# edges_expander_v01.net
KiCad netlist of a schematic drawn in EAGLE
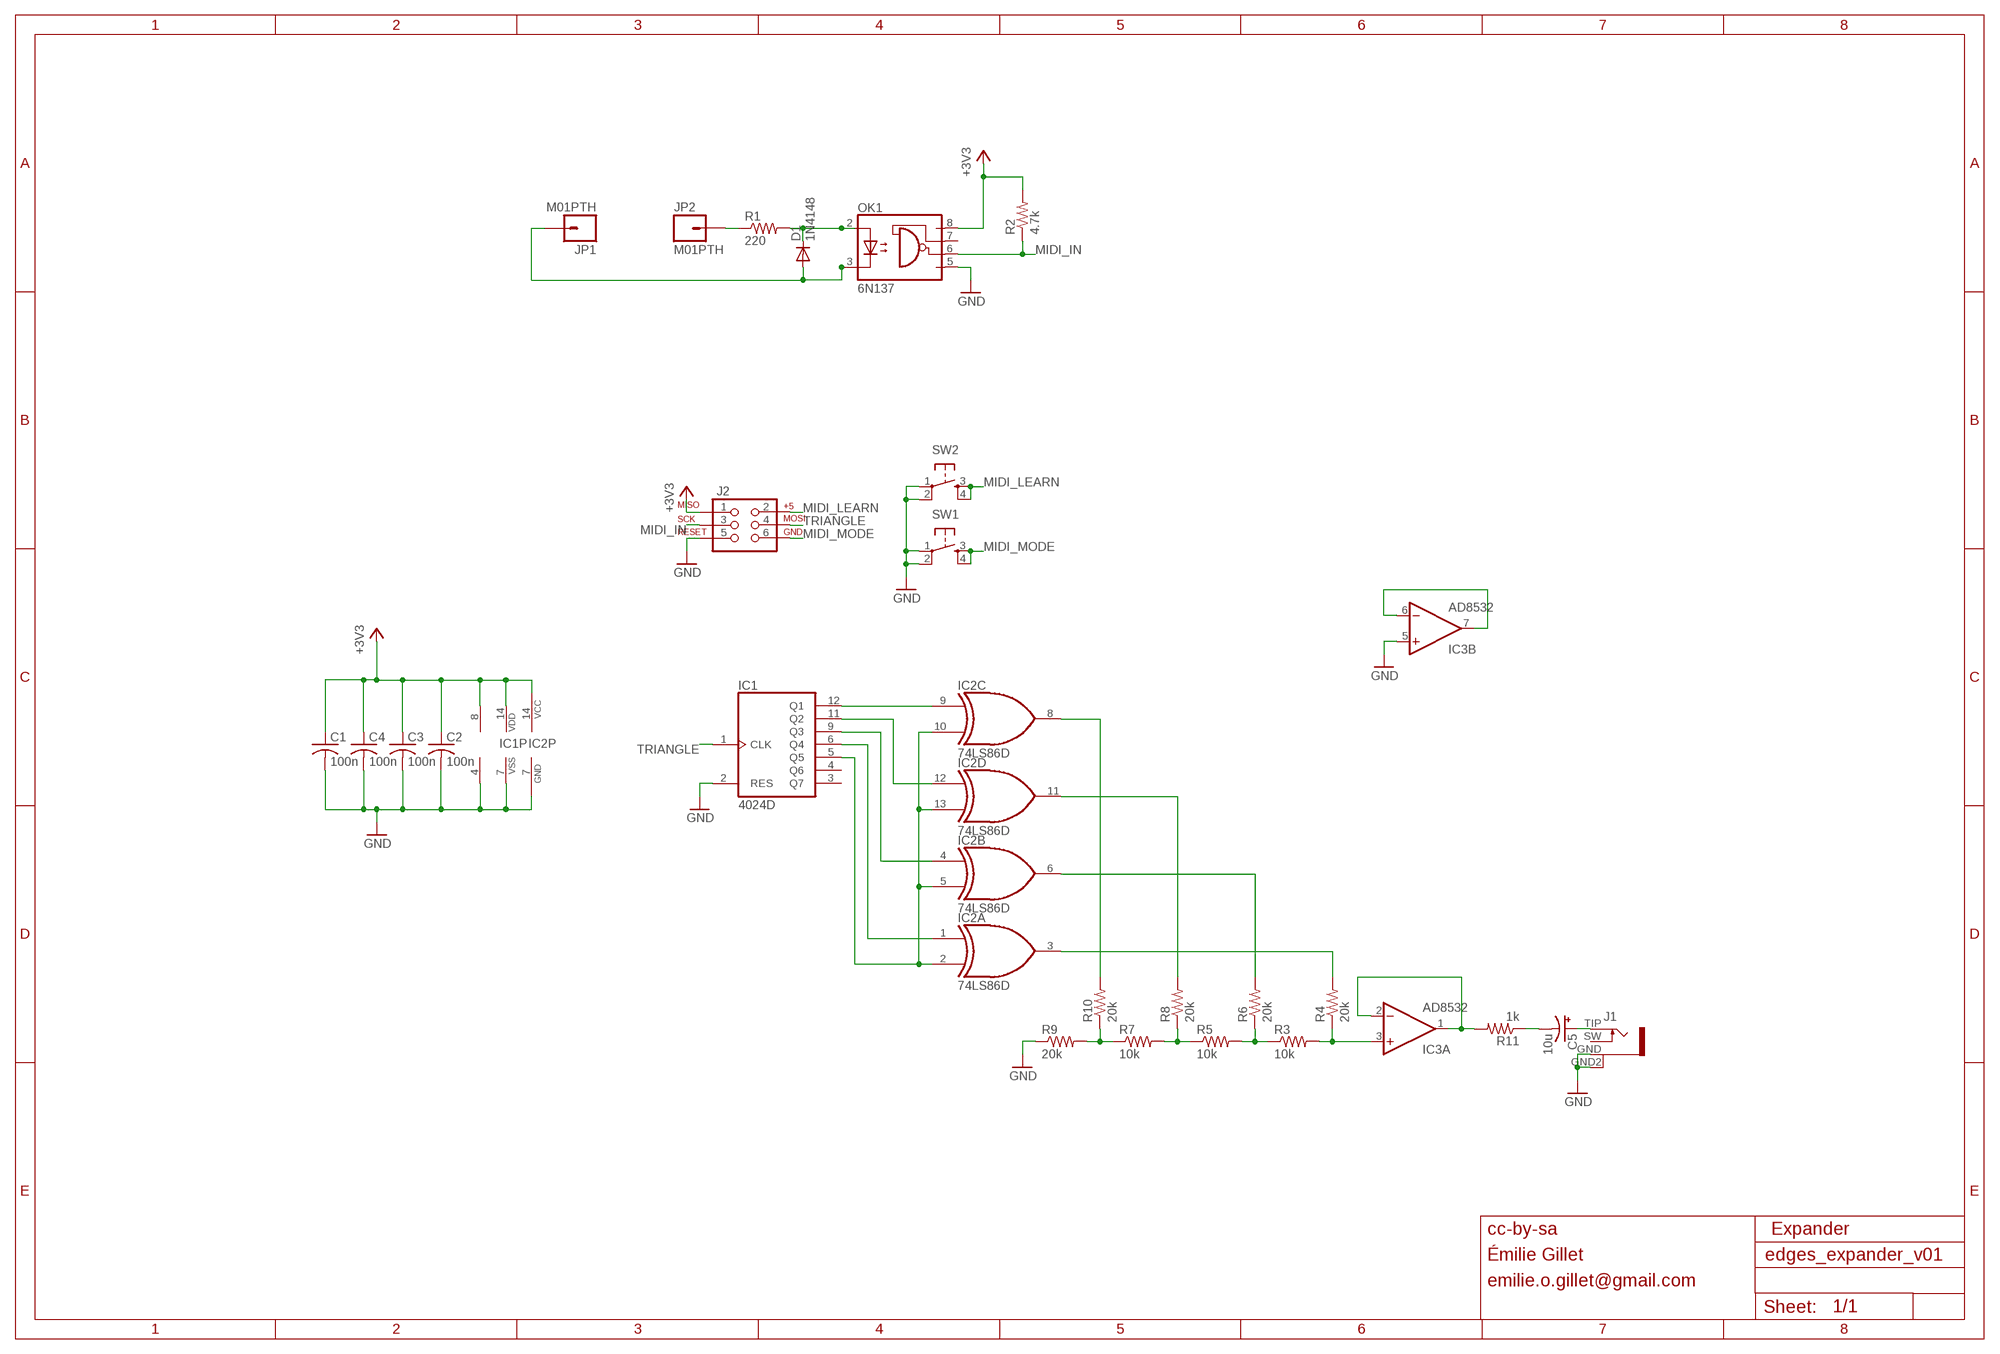
[diagram p0: schematic, sheet 1]

(export (version "E")
  (design (tool "Eeschema 10.0.6"))
  (components
    (comp (ref "C1")
      (value "100n")
      (footprint "eagle-import:C0603")
      (libsource (lib "eagle-import") (part "C-USC0603"))
    )
    (comp (ref "C2")
      (value "100n")
      (footprint "eagle-import:C0603")
      (libsource (lib "eagle-import") (part "C-USC0603"))
    )
    (comp (ref "C3")
      (value "100n")
      (footprint "eagle-import:C0603")
      (libsource (lib "eagle-import") (part "C-USC0603"))
    )
    (comp (ref "C4")
      (value "100n")
      (footprint "eagle-import:C0603")
      (libsource (lib "eagle-import") (part "C-USC0603"))
    )
    (comp (ref "C5")
      (value "10u")
      (footprint "eagle-import:PANASONIC_B")
      (libsource (lib "eagle-import") (part "CPOL-USB"))
    )
    (comp (ref "D1")
      (value "1N4148")
      (footprint "eagle-import:SOD323-W")
      (libsource (lib "eagle-import") (part "DIODE-SOD323-W"))
    )
    (comp (ref "IC1")
      (value "4024D")
      (footprint "eagle-import:SO14")
      (libsource (lib "eagle-import") (part "4024D"))
    )
    (comp (ref "IC2")
      (value "74LS86D")
      (footprint "eagle-import:SO14")
      (libsource (lib "eagle-import") (part "7486DLS"))
    )
    (comp (ref "IC3")
      (value "AD8532")
      (footprint "eagle-import:SO08")
      (libsource (lib "eagle-import") (part "TL072D"))
    )
    (comp (ref "J1")
      (value "PJ301WQP")
      (footprint "eagle-import:WQP_PJ_301BM")
      (libsource (lib "eagle-import") (part "PJ301WQP"))
    )
    (comp (ref "J2")
      (value "AVR_SPI_PRG_6PTH")
      (footprint "eagle-import:2X3")
      (libsource (lib "eagle-import") (part "AVR_SPI_PRG_6PTH"))
    )
    (comp (ref "JP1")
      (value "M01PTH")
      (footprint "eagle-import:1X01")
      (libsource (lib "eagle-import") (part "M01PTH"))
    )
    (comp (ref "JP2")
      (value "M01PTH")
      (footprint "eagle-import:1X01")
      (libsource (lib "eagle-import") (part "M01PTH"))
    )
    (comp (ref "OK1")
      (value "6N137")
      (footprint "eagle-import:DIL8-SMD")
      (libsource (lib "eagle-import") (part "6N137SMT"))
    )
    (comp (ref "R1")
      (value "220")
      (footprint "eagle-import:R0603")
      (libsource (lib "eagle-import") (part "R-US_R0603"))
    )
    (comp (ref "R2")
      (value "4.7k")
      (footprint "eagle-import:R0603")
      (libsource (lib "eagle-import") (part "R-US_R0603"))
    )
    (comp (ref "R3")
      (value "10k")
      (footprint "eagle-import:R0603")
      (libsource (lib "eagle-import") (part "R-US_R0603"))
    )
    (comp (ref "R4")
      (value "20k")
      (footprint "eagle-import:R0603")
      (libsource (lib "eagle-import") (part "R-US_R0603"))
    )
    (comp (ref "R5")
      (value "10k")
      (footprint "eagle-import:R0603")
      (libsource (lib "eagle-import") (part "R-US_R0603"))
    )
    (comp (ref "R6")
      (value "20k")
      (footprint "eagle-import:R0603")
      (libsource (lib "eagle-import") (part "R-US_R0603"))
    )
    (comp (ref "R7")
      (value "10k")
      (footprint "eagle-import:R0603")
      (libsource (lib "eagle-import") (part "R-US_R0603"))
    )
    (comp (ref "R8")
      (value "20k")
      (footprint "eagle-import:R0603")
      (libsource (lib "eagle-import") (part "R-US_R0603"))
    )
    (comp (ref "R9")
      (value "20k")
      (footprint "eagle-import:R0603")
      (libsource (lib "eagle-import") (part "R-US_R0603"))
    )
    (comp (ref "R10")
      (value "20k")
      (footprint "eagle-import:R0603")
      (libsource (lib "eagle-import") (part "R-US_R0603"))
    )
    (comp (ref "R11")
      (value "1k")
      (footprint "eagle-import:R0603")
      (libsource (lib "eagle-import") (part "R-US_R0603"))
    )
    (comp (ref "SW1")
      (value "TAC_SWITCHPTH")
      (footprint "eagle-import:TACTILE-PTH")
      (libsource (lib "eagle-import") (part "TAC_SWITCHPTH"))
    )
    (comp (ref "SW2")
      (value "TAC_SWITCHPTH")
      (footprint "eagle-import:TACTILE-PTH")
      (libsource (lib "eagle-import") (part "TAC_SWITCHPTH"))
    )
  )
  (nets
    (net (code "1") (name "+3V3") (class "Default")
      (node (ref "C1") (pin "1") (pinfunction "1_1") (pintype "passive"))
      (node (ref "C2") (pin "1") (pinfunction "1_1") (pintype "passive"))
      (node (ref "C3") (pin "1") (pinfunction "1_1") (pintype "passive"))
      (node (ref "C4") (pin "1") (pinfunction "1_1") (pintype "passive"))
      (node (ref "IC1") (pin "14") (pinfunction "VDD_14") (pintype "power_in"))
      (node (ref "IC2") (pin "14") (pinfunction "VCC_14") (pintype "power_in"))
      (node (ref "IC3") (pin "8") (pinfunction "V+_8") (pintype "power_in"))
      (node (ref "J2") (pin "1") (pinfunction "1_1") (pintype "passive"))
      (node (ref "OK1") (pin "8") (pinfunction "VCC_8") (pintype "passive"))
      (node (ref "R2") (pin "2") (pinfunction "2_2") (pintype "passive"))
    )
    (net (code "2") (name "/MIDI_IN") (class "Default")
      (node (ref "J2") (pin "3") (pinfunction "3_3") (pintype "passive"))
      (node (ref "OK1") (pin "6") (pinfunction "VO_6") (pintype "passive"))
      (node (ref "R2") (pin "1") (pinfunction "1_1") (pintype "passive"))
    )
    (net (code "3") (name "/MIDI_LEARN") (class "Default")
      (node (ref "J2") (pin "2") (pinfunction "2_2") (pintype "passive"))
      (node (ref "SW2") (pin "3") (pinfunction "3_3") (pintype "passive"))
      (node (ref "SW2") (pin "4") (pinfunction "4_4") (pintype "passive"))
    )
    (net (code "4") (name "/MIDI_MODE") (class "Default")
      (node (ref "J2") (pin "6") (pinfunction "6_6") (pintype "passive"))
      (node (ref "SW1") (pin "3") (pinfunction "3_3") (pintype "passive"))
      (node (ref "SW1") (pin "4") (pinfunction "4_4") (pintype "passive"))
    )
    (net (code "5") (name "/TRIANGLE") (class "Default")
      (node (ref "IC1") (pin "1") (pinfunction "CLK_1") (pintype "input"))
      (node (ref "J2") (pin "4") (pinfunction "4_4") (pintype "passive"))
    )
    (net (code "6") (name "GND") (class "Default")
      (node (ref "C1") (pin "2") (pinfunction "2_2") (pintype "passive"))
      (node (ref "C2") (pin "2") (pinfunction "2_2") (pintype "passive"))
      (node (ref "C3") (pin "2") (pinfunction "2_2") (pintype "passive"))
      (node (ref "C4") (pin "2") (pinfunction "2_2") (pintype "passive"))
      (node (ref "IC1") (pin "2") (pinfunction "RES_2") (pintype "input"))
      (node (ref "IC1") (pin "7") (pinfunction "VSS_7") (pintype "power_in"))
      (node (ref "IC2") (pin "7") (pinfunction "GND_7") (pintype "power_in"))
      (node (ref "IC3") (pin "4") (pinfunction "V-_4") (pintype "power_in"))
      (node (ref "IC3") (pin "5") (pinfunction "+IN_5") (pintype "input"))
      (node (ref "J1") (pin "GND") (pinfunction "1_GND") (pintype "passive"))
      (node (ref "J1") (pin "GND2") (pinfunction "4_GND2") (pintype "passive"))
      (node (ref "J2") (pin "5") (pinfunction "5_5") (pintype "passive"))
      (node (ref "OK1") (pin "5") (pinfunction "GND_5") (pintype "passive"))
      (node (ref "R9") (pin "1") (pinfunction "1_1") (pintype "passive"))
      (node (ref "SW1") (pin "1") (pinfunction "1_1") (pintype "passive"))
      (node (ref "SW1") (pin "2") (pinfunction "2_2") (pintype "passive"))
      (node (ref "SW2") (pin "1") (pinfunction "1_1") (pintype "passive"))
      (node (ref "SW2") (pin "2") (pinfunction "2_2") (pintype "passive"))
    )
    (net (code "7") (name "Net-(C5-Pad-)") (class "Default")
      (node (ref "C5") (pin "-") (pinfunction "-_-") (pintype "passive"))
      (node (ref "R11") (pin "1") (pinfunction "1_1") (pintype "passive"))
    )
    (net (code "8") (name "Net-(IC1A-Q1)") (class "Default")
      (node (ref "IC1") (pin "12") (pinfunction "Q1_12") (pintype "output"))
      (node (ref "IC2") (pin "9") (pinfunction "I0_9") (pintype "input"))
    )
    (net (code "9") (name "Net-(IC1A-Q2)") (class "Default")
      (node (ref "IC1") (pin "11") (pinfunction "Q2_11") (pintype "output"))
      (node (ref "IC2") (pin "12") (pinfunction "I0_12") (pintype "input"))
    )
    (net (code "10") (name "Net-(IC1A-Q3)") (class "Default")
      (node (ref "IC1") (pin "9") (pinfunction "Q3_9") (pintype "output"))
      (node (ref "IC2") (pin "4") (pinfunction "I0_4") (pintype "input"))
    )
    (net (code "11") (name "Net-(IC1A-Q4)") (class "Default")
      (node (ref "IC1") (pin "6") (pinfunction "Q4_6") (pintype "output"))
      (node (ref "IC2") (pin "1") (pinfunction "I0_1") (pintype "input"))
    )
    (net (code "12") (name "Net-(IC1A-Q5)") (class "Default")
      (node (ref "IC1") (pin "5") (pinfunction "Q5_5") (pintype "output"))
      (node (ref "IC2") (pin "10") (pinfunction "I1_10") (pintype "input"))
      (node (ref "IC2") (pin "13") (pinfunction "I1_13") (pintype "input"))
      (node (ref "IC2") (pin "2") (pinfunction "I1_2") (pintype "input"))
      (node (ref "IC2") (pin "5") (pinfunction "I1_5") (pintype "input"))
    )
    (net (code "13") (name "Net-(IC2A-O)") (class "Default")
      (node (ref "IC2") (pin "3") (pinfunction "O_3") (pintype "output"))
      (node (ref "R4") (pin "2") (pinfunction "2_2") (pintype "passive"))
    )
    (net (code "14") (name "Net-(IC2B-O)") (class "Default")
      (node (ref "IC2") (pin "6") (pinfunction "O_6") (pintype "output"))
      (node (ref "R6") (pin "2") (pinfunction "2_2") (pintype "passive"))
    )
    (net (code "15") (name "Net-(IC2C-O)") (class "Default")
      (node (ref "IC2") (pin "8") (pinfunction "O_8") (pintype "output"))
      (node (ref "R10") (pin "2") (pinfunction "2_2") (pintype "passive"))
    )
    (net (code "16") (name "Net-(IC2D-O)") (class "Default")
      (node (ref "IC2") (pin "11") (pinfunction "O_11") (pintype "output"))
      (node (ref "R8") (pin "2") (pinfunction "2_2") (pintype "passive"))
    )
    (net (code "17") (name "Net-(IC3A-+IN)") (class "Default")
      (node (ref "IC3") (pin "3") (pinfunction "+IN_3") (pintype "input"))
      (node (ref "R3") (pin "2") (pinfunction "2_2") (pintype "passive"))
      (node (ref "R4") (pin "1") (pinfunction "1_1") (pintype "passive"))
    )
    (net (code "18") (name "Net-(IC3A--IN)") (class "Default")
      (node (ref "IC3") (pin "1") (pinfunction "OUT_1") (pintype "output"))
      (node (ref "IC3") (pin "2") (pinfunction "-IN_2") (pintype "input"))
      (node (ref "R11") (pin "2") (pinfunction "2_2") (pintype "passive"))
    )
    (net (code "19") (name "Net-(IC3B--IN)") (class "Default")
      (node (ref "IC3") (pin "6") (pinfunction "-IN_6") (pintype "input"))
      (node (ref "IC3") (pin "7") (pinfunction "OUT_7") (pintype "output"))
    )
    (net (code "20") (name "Net-(J1-2)") (class "Default")
      (node (ref "C5") (pin "+") (pinfunction "+_+") (pintype "passive"))
      (node (ref "J1") (pin "TIP") (pinfunction "2_TIP") (pintype "passive"))
    )
    (net (code "21") (name "Net-(JP2-Pad1)") (class "Default")
      (node (ref "JP2") (pin "1") (pinfunction "1_1") (pintype "passive"))
      (node (ref "R1") (pin "1") (pinfunction "1_1") (pintype "passive"))
    )
    (net (code "22") (name "Net-(OK1-A)") (class "Default")
      (node (ref "D1") (pin "C") (pinfunction "C_C") (pintype "passive"))
      (node (ref "OK1") (pin "2") (pinfunction "A_2") (pintype "passive"))
      (node (ref "R1") (pin "2") (pinfunction "2_2") (pintype "passive"))
    )
    (net (code "23") (name "Net-(OK1-C)") (class "Default")
      (node (ref "D1") (pin "A") (pinfunction "A_A") (pintype "passive"))
      (node (ref "JP1") (pin "1") (pinfunction "1_1") (pintype "passive"))
      (node (ref "OK1") (pin "3") (pinfunction "C_3") (pintype "passive"))
    )
    (net (code "24") (name "Net-(R3-Pad1)") (class "Default")
      (node (ref "R3") (pin "1") (pinfunction "1_1") (pintype "passive"))
      (node (ref "R5") (pin "2") (pinfunction "2_2") (pintype "passive"))
      (node (ref "R6") (pin "1") (pinfunction "1_1") (pintype "passive"))
    )
    (net (code "25") (name "Net-(R5-Pad1)") (class "Default")
      (node (ref "R5") (pin "1") (pinfunction "1_1") (pintype "passive"))
      (node (ref "R7") (pin "2") (pinfunction "2_2") (pintype "passive"))
      (node (ref "R8") (pin "1") (pinfunction "1_1") (pintype "passive"))
    )
    (net (code "26") (name "Net-(R10-Pad1)") (class "Default")
      (node (ref "R10") (pin "1") (pinfunction "1_1") (pintype "passive"))
      (node (ref "R7") (pin "1") (pinfunction "1_1") (pintype "passive"))
      (node (ref "R9") (pin "2") (pinfunction "2_2") (pintype "passive"))
    )
    (net (code "27") (name "unconnected-(IC1A-Q6-Pad4)") (class "Default")
      (node (ref "IC1") (pin "4") (pinfunction "Q6_4") (pintype "output"))
    )
    (net (code "28") (name "unconnected-(IC1A-Q7-Pad3)") (class "Default")
      (node (ref "IC1") (pin "3") (pinfunction "Q7_3") (pintype "output"))
    )
    (net (code "29") (name "unconnected-(J1-3-PadSW)") (class "Default")
      (node (ref "J1") (pin "SW") (pinfunction "3_SW") (pintype "passive"))
    )
    (net (code "30") (name "unconnected-(OK1-VE-Pad7)") (class "Default")
      (node (ref "OK1") (pin "7") (pinfunction "VE_7") (pintype "passive"))
    )
  )
)
